# Port.net
KiCad netlist of a schematic drawn in Altium Designer
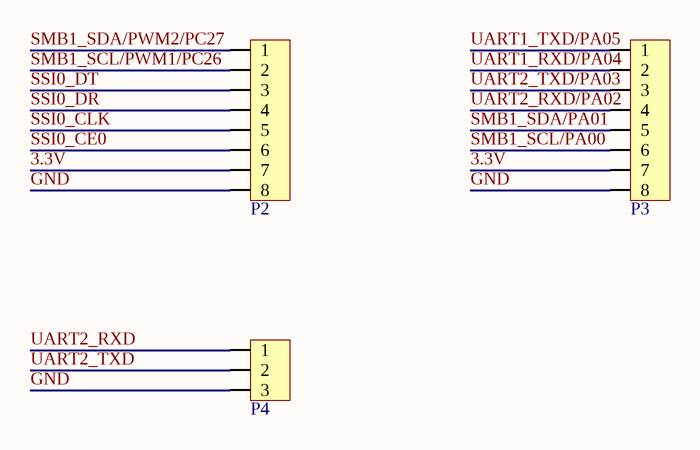
[diagram p0: Port.SchDoc]

(export (version "E")
  (design (tool "Eeschema 10.0.6"))
  (components
    (comp (ref "P2")
      (value "HDR1x8_2.54")
      (footprint "PCB_ConnectorHDR:HDR1X8_2.54_180")
      (description "Header")
      (libsource (lib "SCH_ConnectorHDR") (part "HDR1x8_2.54"))
    )
    (comp (ref "P3")
      (value "HDR1x8_2.54")
      (footprint "PCB_ConnectorHDR:HDR1X8_2.54_180")
      (description "Header")
      (libsource (lib "SCH_ConnectorHDR") (part "HDR1x8_2.54"))
    )
    (comp (ref "P4")
      (value "HDR1x3_2.54")
      (footprint "PCB_ConnectorHDR:HDR1X3_2.54_180")
      (description "Header")
      (libsource (lib "SCH_ConnectorHDR") (part "HDR1x3_2.54"))
    )
  )
  (nets
    (net (code "1") (name "/3.3V") (class "Default")
      (node (ref "P2") (pin "7") (pinfunction "7_7") (pintype "passive"))
      (node (ref "P3") (pin "7") (pinfunction "7_7") (pintype "passive"))
    )
    (net (code "2") (name "/GND") (class "Default")
      (node (ref "P2") (pin "8") (pinfunction "8_8") (pintype "passive"))
      (node (ref "P3") (pin "8") (pinfunction "8_8") (pintype "passive"))
      (node (ref "P4") (pin "3") (pinfunction "3_3") (pintype "passive"))
    )
    (net (code "3") (name "/SMB1_SCL{slash}PA00") (class "Default")
      (node (ref "P3") (pin "6") (pinfunction "6_6") (pintype "passive"))
    )
    (net (code "4") (name "/SMB1_SCL{slash}PWM1{slash}PC26") (class "Default")
      (node (ref "P2") (pin "2") (pinfunction "2_2") (pintype "passive"))
    )
    (net (code "5") (name "/SMB1_SDA{slash}PA01") (class "Default")
      (node (ref "P3") (pin "5") (pinfunction "5_5") (pintype "passive"))
    )
    (net (code "6") (name "/SMB1_SDA{slash}PWM2{slash}PC27") (class "Default")
      (node (ref "P2") (pin "1") (pinfunction "1_1") (pintype "passive"))
    )
    (net (code "7") (name "/SSI0_CE0") (class "Default")
      (node (ref "P2") (pin "6") (pinfunction "6_6") (pintype "passive"))
    )
    (net (code "8") (name "/SSI0_CLK") (class "Default")
      (node (ref "P2") (pin "5") (pinfunction "5_5") (pintype "passive"))
    )
    (net (code "9") (name "/SSI0_DR") (class "Default")
      (node (ref "P2") (pin "4") (pinfunction "4_4") (pintype "passive"))
    )
    (net (code "10") (name "/SSI0_DT") (class "Default")
      (node (ref "P2") (pin "3") (pinfunction "3_3") (pintype "passive"))
    )
    (net (code "11") (name "/UART1_RXD{slash}PA04") (class "Default")
      (node (ref "P3") (pin "2") (pinfunction "2_2") (pintype "passive"))
    )
    (net (code "12") (name "/UART1_TXD{slash}PA05") (class "Default")
      (node (ref "P3") (pin "1") (pinfunction "1_1") (pintype "passive"))
    )
    (net (code "13") (name "/UART2_RXD") (class "Default")
      (node (ref "P4") (pin "1") (pinfunction "1_1") (pintype "passive"))
    )
    (net (code "14") (name "/UART2_RXD{slash}PA02") (class "Default")
      (node (ref "P3") (pin "4") (pinfunction "4_4") (pintype "passive"))
    )
    (net (code "15") (name "/UART2_TXD") (class "Default")
      (node (ref "P4") (pin "2") (pinfunction "2_2") (pintype "passive"))
    )
    (net (code "16") (name "/UART2_TXD{slash}PA03") (class "Default")
      (node (ref "P3") (pin "3") (pinfunction "3_3") (pintype "passive"))
    )
  )
)
